# Modular_Assistive_Technology_Interface.net
KiCad netlist of a schematic drawn in EAGLE
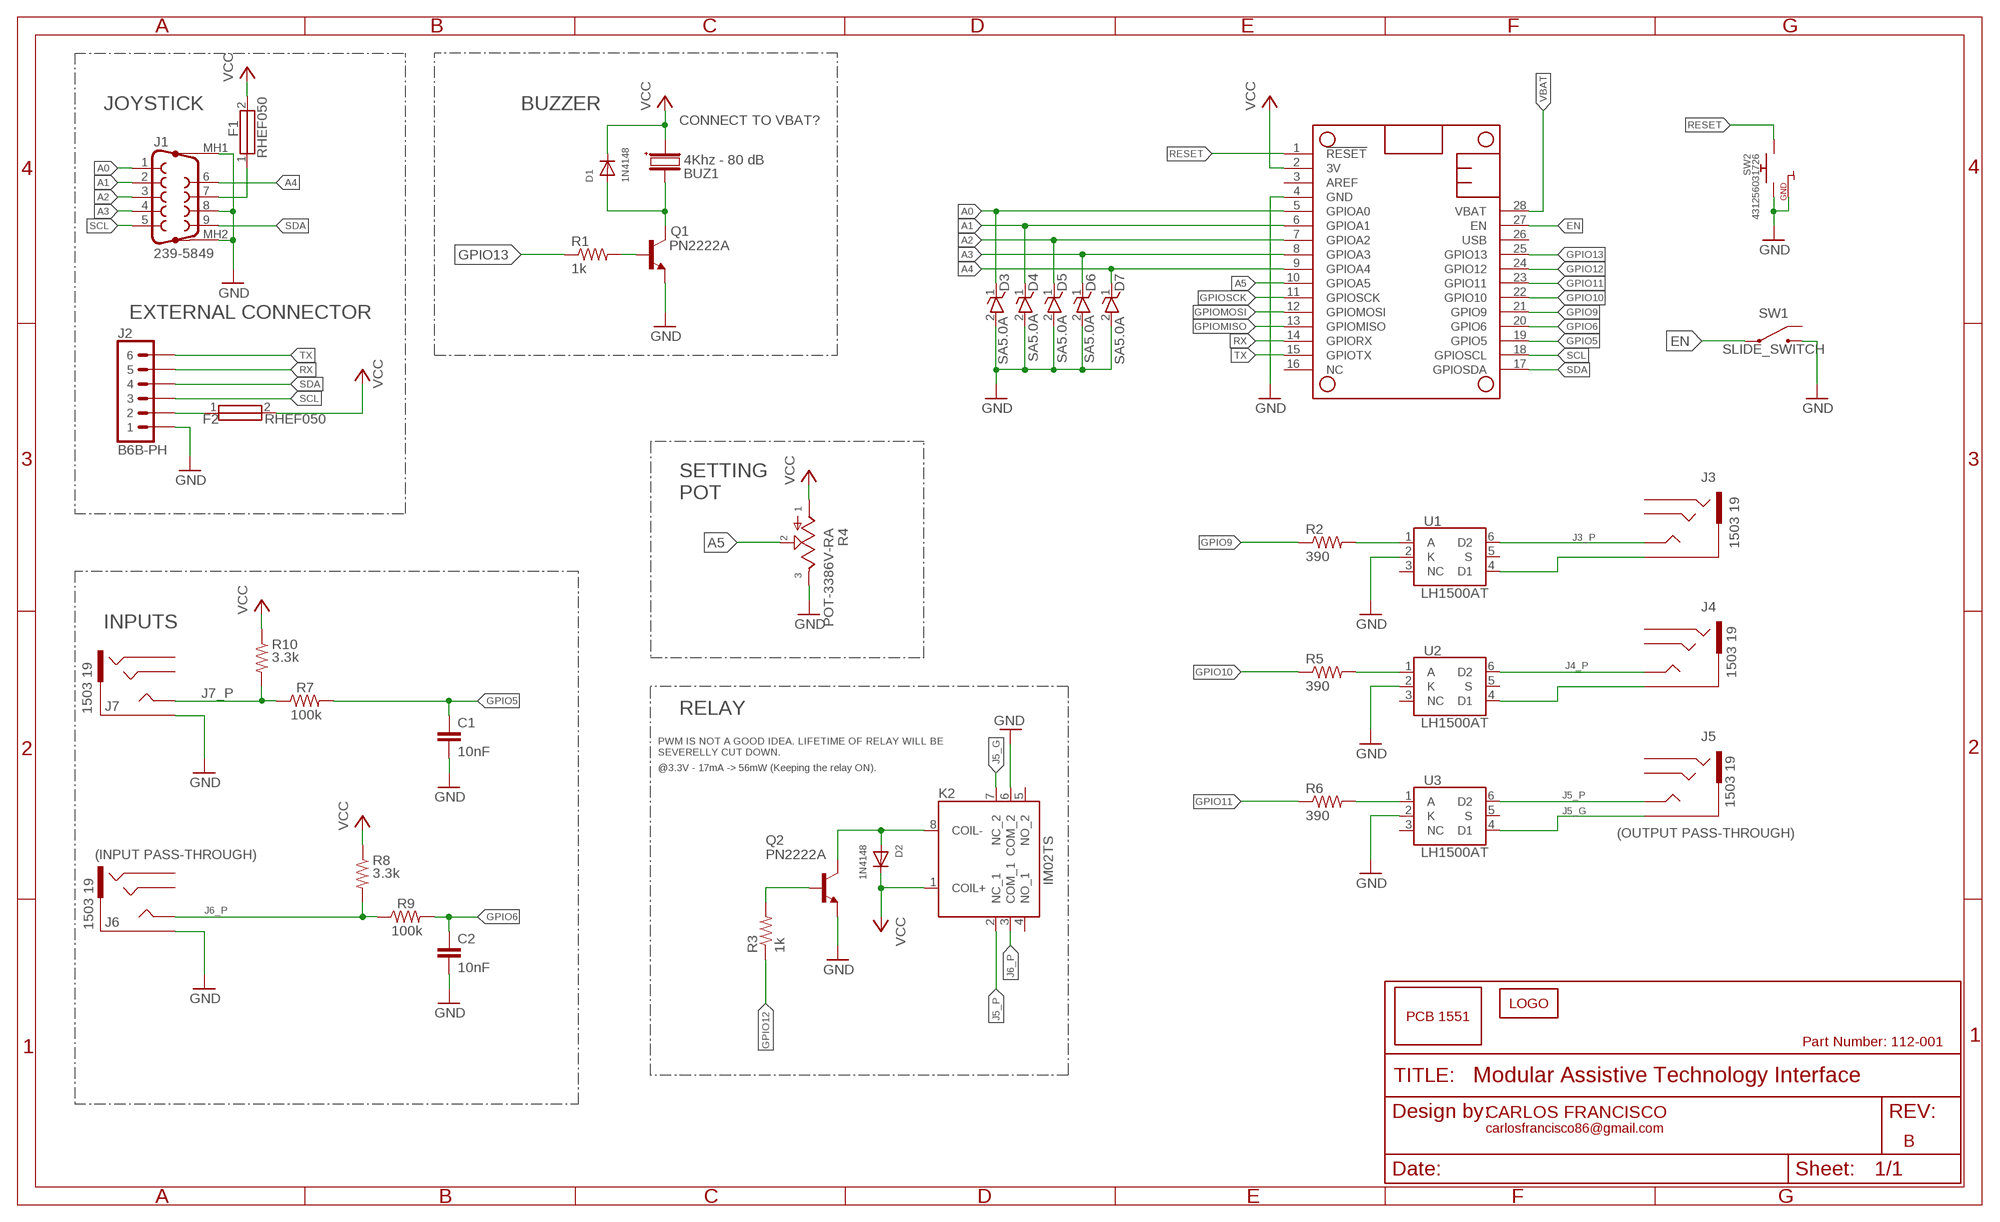
[diagram p0: schematic, sheet 1]

(export (version "E")
  (design (tool "Eeschema 10.0.6"))
  (components
    (comp (ref "BUZ1")
      (value "4Khz - 80 dB")
      (footprint "eagle-import:-511-7620")
      (fields (field (name "MFR") "RS PRO"))
      (libsource (lib "eagle-import") (part "BUZZER-511-7620"))
    )
    (comp (ref "C1")
      (value "10nF")
      (footprint "eagle-import:C025-024X044")
      (libsource (lib "eagle-import") (part "C-EU025-024X044"))
    )
    (comp (ref "C2")
      (value "10nF")
      (footprint "eagle-import:C025-024X044")
      (libsource (lib "eagle-import") (part "C-EU025-024X044"))
    )
    (comp (ref "D1")
      (value "1N4148")
      (footprint "eagle-import:DO-1N4148")
      (fields (field (name "MFR") "ON Semiconductor"))
      (libsource (lib "eagle-import") (part "DIODE-DO-35"))
    )
    (comp (ref "D2")
      (value "1N4148")
      (footprint "eagle-import:DO-1N4148")
      (fields (field (name "MFR") "ON Semiconductor"))
      (libsource (lib "eagle-import") (part "DIODE-DO-35"))
    )
    (comp (ref "D3")
      (value "SA5.0A")
      (footprint "eagle-import:DIOAD1910W86L670D310")
      (fields (field (name "MFR") "Littelfuse"))
      (libsource (lib "eagle-import") (part "ESD_DIODE"))
    )
    (comp (ref "D4")
      (value "SA5.0A")
      (footprint "eagle-import:DIOAD1910W86L670D310")
      (fields (field (name "MFR") "Littelfuse"))
      (libsource (lib "eagle-import") (part "ESD_DIODE"))
    )
    (comp (ref "D5")
      (value "SA5.0A")
      (footprint "eagle-import:DIOAD1910W86L670D310")
      (fields (field (name "MFR") "Littelfuse"))
      (libsource (lib "eagle-import") (part "ESD_DIODE"))
    )
    (comp (ref "D6")
      (value "SA5.0A")
      (footprint "eagle-import:DIOAD1910W86L670D310")
      (fields (field (name "MFR") "Littelfuse"))
      (libsource (lib "eagle-import") (part "ESD_DIODE"))
    )
    (comp (ref "D7")
      (value "SA5.0A")
      (footprint "eagle-import:DIOAD1910W86L670D310")
      (fields (field (name "MFR") "Littelfuse"))
      (libsource (lib "eagle-import") (part "ESD_DIODE"))
    )
    (comp (ref "F1")
      (value "RHEF050")
      (footprint "eagle-import:RHEF050")
      (libsource (lib "eagle-import") (part "RHEF050"))
    )
    (comp (ref "F2")
      (value "RHEF050")
      (footprint "eagle-import:RHEF050")
      (libsource (lib "eagle-import") (part "RHEF050"))
    )
    (comp (ref "J1")
      (value "239-5849")
      (footprint "eagle-import:DB9_PLUG_SLOT")
      (fields (field (name "MFR") "RS Pro"))
      (libsource (lib "eagle-import") (part "DB9_MALE-SLOTS"))
    )
    (comp (ref "J2")
      (value "B6B-PH")
      (footprint "eagle-import:SHDR6W50P0X200_1X6_990X450X600")
      (fields (field (name "MFR") "JST"))
      (libsource (lib "eagle-import") (part "CONN_06-B6B-PH"))
    )
    (comp (ref "J3")
      (value "1503 19")
      (footprint "eagle-import:1503-19")
      (fields (field (name "MFR") "Lumberg"))
      (libsource (lib "eagle-import") (part "STEREO_JACK-1503-19"))
    )
    (comp (ref "J4")
      (value "1503 19")
      (footprint "eagle-import:1503-19")
      (fields (field (name "MFR") "Lumberg"))
      (libsource (lib "eagle-import") (part "STEREO_JACK-1503-19"))
    )
    (comp (ref "J5")
      (value "1503 19")
      (footprint "eagle-import:1503-19")
      (fields (field (name "MFR") "Lumberg"))
      (libsource (lib "eagle-import") (part "STEREO_JACK-1503-19"))
    )
    (comp (ref "J6")
      (value "1503 19")
      (footprint "eagle-import:1503-19")
      (fields (field (name "MFR") "Lumberg"))
      (libsource (lib "eagle-import") (part "STEREO_JACK-1503-19"))
    )
    (comp (ref "J7")
      (value "1503 19")
      (footprint "eagle-import:1503-19")
      (fields (field (name "MFR") "Lumberg"))
      (libsource (lib "eagle-import") (part "STEREO_JACK-1503-19"))
    )
    (comp (ref "K2")
      (value "IM02TS")
      (footprint "eagle-import:IM03TS114620378")
      (fields (field (name "MANUFACTURER_PART_NUMBER") "IM03TS 1-1462037-8"))
      (libsource (lib "eagle-import") (part "IM02TS"))
    )
    (comp (ref "MS1")
      (value "FEATHERWING_NODIM")
      (footprint "eagle-import:FEATHERWING_DIM")
      (libsource (lib "eagle-import") (part "FEATHERWING_NODIM"))
    )
    (comp (ref "Q1")
      (value "PN2222A")
      (footprint "eagle-import:TO92-EBC-OVAL")
      (fields (field (name "MFR") "ON Semiconductor"))
      (libsource (lib "eagle-import") (part "NPN-TO-92"))
    )
    (comp (ref "Q2")
      (value "PN2222A")
      (footprint "eagle-import:TO92-EBC-OVAL")
      (fields (field (name "MFR") "ON Semiconductor"))
      (libsource (lib "eagle-import") (part "NPN-TO-92"))
    )
    (comp (ref "R1")
      (value "1k")
      (footprint "eagle-import:0207_10")
      (libsource (lib "eagle-import") (part "R-US_0207/10"))
    )
    (comp (ref "R2")
      (value "390")
      (footprint "eagle-import:0207_10")
      (libsource (lib "eagle-import") (part "R-US_0207/10"))
    )
    (comp (ref "R3")
      (value "1k")
      (footprint "eagle-import:0207_10")
      (libsource (lib "eagle-import") (part "R-US_0207/10"))
    )
    (comp (ref "R4")
      (value "POT-3386V-RA")
      (footprint "eagle-import:3386V1103LF")
      (libsource (lib "eagle-import") (part "POT-3386V-RA"))
    )
    (comp (ref "R5")
      (value "390")
      (footprint "eagle-import:0207_10")
      (libsource (lib "eagle-import") (part "R-US_0207/10"))
    )
    (comp (ref "R6")
      (value "390")
      (footprint "eagle-import:0207_10")
      (libsource (lib "eagle-import") (part "R-US_0207/10"))
    )
    (comp (ref "R7")
      (value "100k")
      (footprint "eagle-import:0207_10")
      (libsource (lib "eagle-import") (part "R-US_0207/10"))
    )
    (comp (ref "R8")
      (value "3.3k")
      (footprint "eagle-import:0207_10")
      (libsource (lib "eagle-import") (part "R-US_0207/10"))
    )
    (comp (ref "R9")
      (value "100k")
      (footprint "eagle-import:0207_10")
      (libsource (lib "eagle-import") (part "R-US_0207/10"))
    )
    (comp (ref "R10")
      (value "3.3k")
      (footprint "eagle-import:0207_10")
      (libsource (lib "eagle-import") (part "R-US_0207/10"))
    )
    (comp (ref "SW1")
      (value "SLIDE_SWITCH")
      (footprint "eagle-import:OS102011MA1QN1")
      (fields
        (field (name "ARROW_PART_NUMBER") "OS102011MA1QN1")
        (field (name "MOUSER_PART_NUMBER") "611-OS102011MA1QN1")
      )
      (libsource (lib "eagle-import") (part "SLIDE_SWITCH"))
    )
    (comp (ref "SW2")
      (value "431256031726")
      (footprint "eagle-import:SERIES95C_RA")
      (fields (field (name "MFR") "Wurth Elektronik"))
      (libsource (lib "eagle-import") (part "SPST-RA"))
    )
    (comp (ref "U$2")
      (value "LOGO-10MM")
      (footprint "eagle-import:LOGO_10MM")
      (libsource (lib "eagle-import") (part "LOGO-10MM"))
    )
    (comp (ref "U$3")
      (value "PCB_1551-1551")
      (footprint "eagle-import:PCB")
      (libsource (lib "eagle-import") (part "PCB_1551-1551"))
    )
    (comp (ref "U1")
      (value "LH1500AT")
      (footprint "eagle-import:DIP762W47P254L880H410Q6N")
      (fields (field (name "MFR") "Vishay"))
      (libsource (lib "eagle-import") (part "SSR-LH1500AT"))
    )
    (comp (ref "U2")
      (value "LH1500AT")
      (footprint "eagle-import:DIP762W47P254L880H410Q6N")
      (fields (field (name "MFR") "Vishay"))
      (libsource (lib "eagle-import") (part "SSR-LH1500AT"))
    )
    (comp (ref "U3")
      (value "LH1500AT")
      (footprint "eagle-import:DIP762W47P254L880H410Q6N")
      (fields (field (name "MFR") "Vishay"))
      (libsource (lib "eagle-import") (part "SSR-LH1500AT"))
    )
  )
  (nets
    (net (code "1") (name "/J3_P") (class "Default")
      (node (ref "J3") (pin "4") (pinfunction "4_4") (pintype "bidirectional"))
      (node (ref "J3") (pin "5") (pinfunction "4_5") (pintype "bidirectional"))
      (node (ref "U1") (pin "6") (pinfunction "D2_6") (pintype "bidirectional"))
    )
    (net (code "2") (name "/J4_P") (class "Default")
      (node (ref "J4") (pin "4") (pinfunction "4_4") (pintype "bidirectional"))
      (node (ref "J4") (pin "5") (pinfunction "4_5") (pintype "bidirectional"))
      (node (ref "U2") (pin "6") (pinfunction "D2_6") (pintype "bidirectional"))
    )
    (net (code "3") (name "/J7_P") (class "Default")
      (node (ref "J7") (pin "4") (pinfunction "4_4") (pintype "bidirectional"))
      (node (ref "J7") (pin "5") (pinfunction "4_5") (pintype "bidirectional"))
      (node (ref "R10") (pin "2") (pinfunction "2_2") (pintype "passive"))
      (node (ref "R7") (pin "1") (pinfunction "1_1") (pintype "passive"))
    )
    (net (code "4") (name "/USB") (class "Default")
      (node (ref "MS1") (pin "26") (pinfunction "USB_26") (pintype "power_in"))
    )
    (net (code "5") (name "A0") (class "Default")
      (node (ref "D3") (pin "1") (pinfunction "K_1") (pintype "bidirectional"))
      (node (ref "J1") (pin "1") (pinfunction "1_1") (pintype "passive"))
      (node (ref "MS1") (pin "5") (pinfunction "GPIOA0_5") (pintype "bidirectional"))
    )
    (net (code "6") (name "A1") (class "Default")
      (node (ref "D4") (pin "1") (pinfunction "K_1") (pintype "bidirectional"))
      (node (ref "J1") (pin "2") (pinfunction "2_2") (pintype "passive"))
      (node (ref "MS1") (pin "6") (pinfunction "GPIOA1_6") (pintype "bidirectional"))
    )
    (net (code "7") (name "A2") (class "Default")
      (node (ref "D5") (pin "1") (pinfunction "K_1") (pintype "bidirectional"))
      (node (ref "J1") (pin "3") (pinfunction "3_3") (pintype "passive"))
      (node (ref "MS1") (pin "7") (pinfunction "GPIOA2_7") (pintype "bidirectional"))
    )
    (net (code "8") (name "A3") (class "Default")
      (node (ref "D6") (pin "1") (pinfunction "K_1") (pintype "bidirectional"))
      (node (ref "J1") (pin "4") (pinfunction "4_4") (pintype "passive"))
      (node (ref "MS1") (pin "8") (pinfunction "GPIOA3_8") (pintype "bidirectional"))
    )
    (net (code "9") (name "A4") (class "Default")
      (node (ref "D7") (pin "1") (pinfunction "K_1") (pintype "bidirectional"))
      (node (ref "J1") (pin "6") (pinfunction "6_6") (pintype "passive"))
      (node (ref "MS1") (pin "9") (pinfunction "GPIOA4_9") (pintype "bidirectional"))
    )
    (net (code "10") (name "A5") (class "Default")
      (node (ref "MS1") (pin "10") (pinfunction "GPIOA5_10") (pintype "bidirectional"))
      (node (ref "R4") (pin "2") (pinfunction "2_2") (pintype "passive"))
    )
    (net (code "11") (name "EN") (class "Default")
      (node (ref "MS1") (pin "27") (pinfunction "EN_27") (pintype "passive"))
      (node (ref "SW1") (pin "2") (pinfunction "2_2") (pintype "passive"))
    )
    (net (code "12") (name "GND") (class "Default")
      (node (ref "C1") (pin "2") (pinfunction "2_2") (pintype "passive"))
      (node (ref "C2") (pin "2") (pinfunction "2_2") (pintype "passive"))
      (node (ref "D3") (pin "2") (pinfunction "A_2") (pintype "bidirectional"))
      (node (ref "D4") (pin "2") (pinfunction "A_2") (pintype "bidirectional"))
      (node (ref "D5") (pin "2") (pinfunction "A_2") (pintype "bidirectional"))
      (node (ref "D6") (pin "2") (pinfunction "A_2") (pintype "bidirectional"))
      (node (ref "D7") (pin "2") (pinfunction "A_2") (pintype "bidirectional"))
      (node (ref "J1") (pin "8") (pinfunction "8_8") (pintype "passive"))
      (node (ref "J1") (pin "MH1") (pinfunction "G1_MH1") (pintype "passive"))
      (node (ref "J1") (pin "MH2") (pinfunction "G2_MH2") (pintype "passive"))
      (node (ref "J2") (pin "1") (pinfunction "1_1") (pintype "passive"))
      (node (ref "J6") (pin "1") (pinfunction "1_1") (pintype "bidirectional"))
      (node (ref "J7") (pin "1") (pinfunction "1_1") (pintype "bidirectional"))
      (node (ref "K2") (pin "6") (pinfunction "COM_2_6") (pintype "bidirectional"))
      (node (ref "MS1") (pin "4") (pinfunction "GND_4") (pintype "power_in"))
      (node (ref "Q1") (pin "E") (pinfunction "E_E") (pintype "passive"))
      (node (ref "Q2") (pin "E") (pinfunction "E_E") (pintype "passive"))
      (node (ref "R4") (pin "3") (pinfunction "3_3") (pintype "passive"))
      (node (ref "SW1") (pin "1") (pinfunction "1_1") (pintype "passive"))
      (node (ref "SW2") (pin "F1") (pinfunction "GND_F1") (pintype "power_in"))
      (node (ref "SW2") (pin "F2") (pinfunction "GND_F2") (pintype "power_in"))
      (node (ref "SW2") (pin "T2") (pinfunction "SW2_T2") (pintype "passive"))
      (node (ref "U1") (pin "2") (pinfunction "K_2") (pintype "bidirectional"))
      (node (ref "U2") (pin "2") (pinfunction "K_2") (pintype "bidirectional"))
      (node (ref "U3") (pin "2") (pinfunction "K_2") (pintype "bidirectional"))
    )
    (net (code "13") (name "GPIO5") (class "Default")
      (node (ref "C1") (pin "1") (pinfunction "1_1") (pintype "passive"))
      (node (ref "MS1") (pin "19") (pinfunction "GPIO5_19") (pintype "bidirectional"))
      (node (ref "R7") (pin "2") (pinfunction "2_2") (pintype "passive"))
    )
    (net (code "14") (name "GPIO6") (class "Default")
      (node (ref "C2") (pin "1") (pinfunction "1_1") (pintype "passive"))
      (node (ref "MS1") (pin "20") (pinfunction "GPIO6_20") (pintype "bidirectional"))
      (node (ref "R9") (pin "2") (pinfunction "2_2") (pintype "passive"))
    )
    (net (code "15") (name "GPIO9") (class "Default")
      (node (ref "MS1") (pin "21") (pinfunction "GPIO9_21") (pintype "bidirectional"))
      (node (ref "R2") (pin "1") (pinfunction "1_1") (pintype "passive"))
    )
    (net (code "16") (name "GPIO10") (class "Default")
      (node (ref "MS1") (pin "22") (pinfunction "GPIO10_22") (pintype "bidirectional"))
      (node (ref "R5") (pin "1") (pinfunction "1_1") (pintype "passive"))
    )
    (net (code "17") (name "GPIO11") (class "Default")
      (node (ref "MS1") (pin "23") (pinfunction "GPIO11_23") (pintype "bidirectional"))
      (node (ref "R6") (pin "1") (pinfunction "1_1") (pintype "passive"))
    )
    (net (code "18") (name "GPIO12") (class "Default")
      (node (ref "MS1") (pin "24") (pinfunction "GPIO12_24") (pintype "bidirectional"))
      (node (ref "R3") (pin "1") (pinfunction "1_1") (pintype "passive"))
    )
    (net (code "19") (name "GPIO13") (class "Default")
      (node (ref "MS1") (pin "25") (pinfunction "GPIO13_25") (pintype "bidirectional"))
      (node (ref "R1") (pin "1") (pinfunction "1_1") (pintype "passive"))
    )
    (net (code "20") (name "GPIOMISO") (class "Default")
      (node (ref "MS1") (pin "13") (pinfunction "GPIOMISO_13") (pintype "bidirectional"))
    )
    (net (code "21") (name "GPIOMOSI") (class "Default")
      (node (ref "MS1") (pin "12") (pinfunction "GPIOMOSI_12") (pintype "bidirectional"))
    )
    (net (code "22") (name "GPIOSCK") (class "Default")
      (node (ref "MS1") (pin "11") (pinfunction "GPIOSCK_11") (pintype "bidirectional"))
    )
    (net (code "23") (name "J5_G") (class "Default")
      (node (ref "J5") (pin "1") (pinfunction "1_1") (pintype "bidirectional"))
      (node (ref "K2") (pin "7") (pinfunction "NC_2_7") (pintype "bidirectional"))
      (node (ref "U3") (pin "4") (pinfunction "D1_4") (pintype "bidirectional"))
    )
    (net (code "24") (name "J5_P") (class "Default")
      (node (ref "J5") (pin "4") (pinfunction "4_4") (pintype "bidirectional"))
      (node (ref "J5") (pin "5") (pinfunction "4_5") (pintype "bidirectional"))
      (node (ref "K2") (pin "2") (pinfunction "NC_1_2") (pintype "bidirectional"))
      (node (ref "U3") (pin "6") (pinfunction "D2_6") (pintype "bidirectional"))
    )
    (net (code "25") (name "J6_P") (class "Default")
      (node (ref "J6") (pin "4") (pinfunction "4_4") (pintype "bidirectional"))
      (node (ref "J6") (pin "5") (pinfunction "4_5") (pintype "bidirectional"))
      (node (ref "K2") (pin "3") (pinfunction "COM_1_3") (pintype "bidirectional"))
      (node (ref "R8") (pin "2") (pinfunction "2_2") (pintype "passive"))
      (node (ref "R9") (pin "1") (pinfunction "1_1") (pintype "passive"))
    )
    (net (code "26") (name "Net-(BUZ1-Pad-)") (class "Default")
      (node (ref "BUZ1") (pin "-") (pinfunction "-_-") (pintype "passive"))
      (node (ref "D1") (pin "A") (pinfunction "A_A") (pintype "passive"))
      (node (ref "Q1") (pin "C") (pinfunction "C_C") (pintype "passive"))
    )
    (net (code "27") (name "Net-(F1-Pad1)") (class "Default")
      (node (ref "F1") (pin "1") (pinfunction "1_1") (pintype "bidirectional"))
      (node (ref "J1") (pin "7") (pinfunction "7_7") (pintype "passive"))
    )
    (net (code "28") (name "Net-(F2-Pad1)") (class "Default")
      (node (ref "F2") (pin "1") (pinfunction "1_1") (pintype "bidirectional"))
      (node (ref "J2") (pin "2") (pinfunction "2_2") (pintype "passive"))
    )
    (net (code "29") (name "Net-(K2-COIL-)") (class "Default")
      (node (ref "D2") (pin "A") (pinfunction "A_A") (pintype "passive"))
      (node (ref "K2") (pin "8") (pinfunction "COIL-_8") (pintype "bidirectional"))
      (node (ref "Q2") (pin "C") (pinfunction "C_C") (pintype "passive"))
    )
    (net (code "30") (name "Net-(Q1-PadB)") (class "Default")
      (node (ref "Q1") (pin "B") (pinfunction "B_B") (pintype "passive"))
      (node (ref "R1") (pin "2") (pinfunction "2_2") (pintype "passive"))
    )
    (net (code "31") (name "Net-(Q2-PadB)") (class "Default")
      (node (ref "Q2") (pin "B") (pinfunction "B_B") (pintype "passive"))
      (node (ref "R3") (pin "2") (pinfunction "2_2") (pintype "passive"))
    )
    (net (code "32") (name "Net-(U1-A)") (class "Default")
      (node (ref "R2") (pin "2") (pinfunction "2_2") (pintype "passive"))
      (node (ref "U1") (pin "1") (pinfunction "A_1") (pintype "bidirectional"))
    )
    (net (code "33") (name "Net-(U1-D1)") (class "Default")
      (node (ref "J3") (pin "1") (pinfunction "1_1") (pintype "bidirectional"))
      (node (ref "U1") (pin "4") (pinfunction "D1_4") (pintype "bidirectional"))
    )
    (net (code "34") (name "Net-(U2-A)") (class "Default")
      (node (ref "R5") (pin "2") (pinfunction "2_2") (pintype "passive"))
      (node (ref "U2") (pin "1") (pinfunction "A_1") (pintype "bidirectional"))
    )
    (net (code "35") (name "Net-(U2-D1)") (class "Default")
      (node (ref "J4") (pin "1") (pinfunction "1_1") (pintype "bidirectional"))
      (node (ref "U2") (pin "4") (pinfunction "D1_4") (pintype "bidirectional"))
    )
    (net (code "36") (name "Net-(U3-A)") (class "Default")
      (node (ref "R6") (pin "2") (pinfunction "2_2") (pintype "passive"))
      (node (ref "U3") (pin "1") (pinfunction "A_1") (pintype "bidirectional"))
    )
    (net (code "37") (name "RESET") (class "Default")
      (node (ref "MS1") (pin "1") (pinfunction "~{RESET}_1") (pintype "input"))
      (node (ref "SW2") (pin "T1") (pinfunction "SW1_T1") (pintype "passive"))
    )
    (net (code "38") (name "RX") (class "Default")
      (node (ref "J2") (pin "5") (pinfunction "5_5") (pintype "passive"))
      (node (ref "MS1") (pin "14") (pinfunction "GPIORX_14") (pintype "bidirectional"))
    )
    (net (code "39") (name "SCL") (class "Default")
      (node (ref "J1") (pin "5") (pinfunction "5_5") (pintype "passive"))
      (node (ref "J2") (pin "3") (pinfunction "3_3") (pintype "passive"))
      (node (ref "MS1") (pin "18") (pinfunction "GPIOSCL_18") (pintype "bidirectional"))
    )
    (net (code "40") (name "SDA") (class "Default")
      (node (ref "J1") (pin "9") (pinfunction "9_9") (pintype "passive"))
      (node (ref "J2") (pin "4") (pinfunction "4_4") (pintype "passive"))
      (node (ref "MS1") (pin "17") (pinfunction "GPIOSDA_17") (pintype "bidirectional"))
    )
    (net (code "41") (name "TX") (class "Default")
      (node (ref "J2") (pin "6") (pinfunction "6_6") (pintype "passive"))
      (node (ref "MS1") (pin "15") (pinfunction "GPIOTX_15") (pintype "bidirectional"))
    )
    (net (code "42") (name "VBAT") (class "Default")
      (node (ref "MS1") (pin "28") (pinfunction "VBAT_28") (pintype "power_in"))
    )
    (net (code "43") (name "VCC") (class "Default")
      (node (ref "BUZ1") (pin "+") (pinfunction "+_+") (pintype "passive"))
      (node (ref "D1") (pin "C") (pinfunction "C_C") (pintype "passive"))
      (node (ref "D2") (pin "C") (pinfunction "C_C") (pintype "passive"))
      (node (ref "F1") (pin "2") (pinfunction "2_2") (pintype "bidirectional"))
      (node (ref "F2") (pin "2") (pinfunction "2_2") (pintype "bidirectional"))
      (node (ref "K2") (pin "1") (pinfunction "COIL+_1") (pintype "bidirectional"))
      (node (ref "MS1") (pin "2") (pinfunction "3V_2") (pintype "power_in"))
      (node (ref "R10") (pin "1") (pinfunction "1_1") (pintype "passive"))
      (node (ref "R4") (pin "1") (pinfunction "1_1") (pintype "passive"))
      (node (ref "R8") (pin "1") (pinfunction "1_1") (pintype "passive"))
    )
    (net (code "44") (name "unconnected-(J3-Pad2)") (class "Default")
      (node (ref "J3") (pin "2") (pinfunction "2_2") (pintype "bidirectional"))
    )
    (net (code "45") (name "unconnected-(J3-Pad3)") (class "Default")
      (node (ref "J3") (pin "3") (pinfunction "3_3") (pintype "bidirectional"))
    )
    (net (code "46") (name "unconnected-(J4-Pad2)") (class "Default")
      (node (ref "J4") (pin "2") (pinfunction "2_2") (pintype "bidirectional"))
    )
    (net (code "47") (name "unconnected-(J4-Pad3)") (class "Default")
      (node (ref "J4") (pin "3") (pinfunction "3_3") (pintype "bidirectional"))
    )
    (net (code "48") (name "unconnected-(J5-Pad2)") (class "Default")
      (node (ref "J5") (pin "2") (pinfunction "2_2") (pintype "bidirectional"))
    )
    (net (code "49") (name "unconnected-(J5-Pad3)") (class "Default")
      (node (ref "J5") (pin "3") (pinfunction "3_3") (pintype "bidirectional"))
    )
    (net (code "50") (name "unconnected-(J6-Pad2)") (class "Default")
      (node (ref "J6") (pin "2") (pinfunction "2_2") (pintype "bidirectional"))
    )
    (net (code "51") (name "unconnected-(J6-Pad3)") (class "Default")
      (node (ref "J6") (pin "3") (pinfunction "3_3") (pintype "bidirectional"))
    )
    (net (code "52") (name "unconnected-(J7-Pad2)") (class "Default")
      (node (ref "J7") (pin "2") (pinfunction "2_2") (pintype "bidirectional"))
    )
    (net (code "53") (name "unconnected-(J7-Pad3)") (class "Default")
      (node (ref "J7") (pin "3") (pinfunction "3_3") (pintype "bidirectional"))
    )
    (net (code "54") (name "unconnected-(K2-NO_1-Pad4)") (class "Default")
      (node (ref "K2") (pin "4") (pinfunction "NO_1_4") (pintype "bidirectional"))
    )
    (net (code "55") (name "unconnected-(K2-NO_2-Pad5)") (class "Default")
      (node (ref "K2") (pin "5") (pinfunction "NO_2_5") (pintype "bidirectional"))
    )
    (net (code "56") (name "unconnected-(MS1-AREF-Pad3)") (class "Default")
      (node (ref "MS1") (pin "3") (pinfunction "AREF_3") (pintype "passive"))
    )
    (net (code "57") (name "unconnected-(MS1-NC-Pad16)") (class "Default")
      (node (ref "MS1") (pin "16") (pinfunction "NC_16") (pintype "passive"))
    )
    (net (code "58") (name "unconnected-(SW1-Pad3)") (class "Default")
      (node (ref "SW1") (pin "3") (pinfunction "3_3") (pintype "passive"))
    )
    (net (code "59") (name "unconnected-(U1-NC-Pad3)") (class "Default")
      (node (ref "U1") (pin "3") (pinfunction "NC_3") (pintype "no_connect"))
    )
    (net (code "60") (name "unconnected-(U1-S-Pad5)") (class "Default")
      (node (ref "U1") (pin "5") (pinfunction "S_5") (pintype "bidirectional"))
    )
    (net (code "61") (name "unconnected-(U2-NC-Pad3)") (class "Default")
      (node (ref "U2") (pin "3") (pinfunction "NC_3") (pintype "no_connect"))
    )
    (net (code "62") (name "unconnected-(U2-S-Pad5)") (class "Default")
      (node (ref "U2") (pin "5") (pinfunction "S_5") (pintype "bidirectional"))
    )
    (net (code "63") (name "unconnected-(U3-NC-Pad3)") (class "Default")
      (node (ref "U3") (pin "3") (pinfunction "NC_3") (pintype "no_connect"))
    )
    (net (code "64") (name "unconnected-(U3-S-Pad5)") (class "Default")
      (node (ref "U3") (pin "5") (pinfunction "S_5") (pintype "bidirectional"))
    )
  )
)
